# Argo_v2_Project.net
KiCad netlist of a schematic drawn in EasyEDA Pro
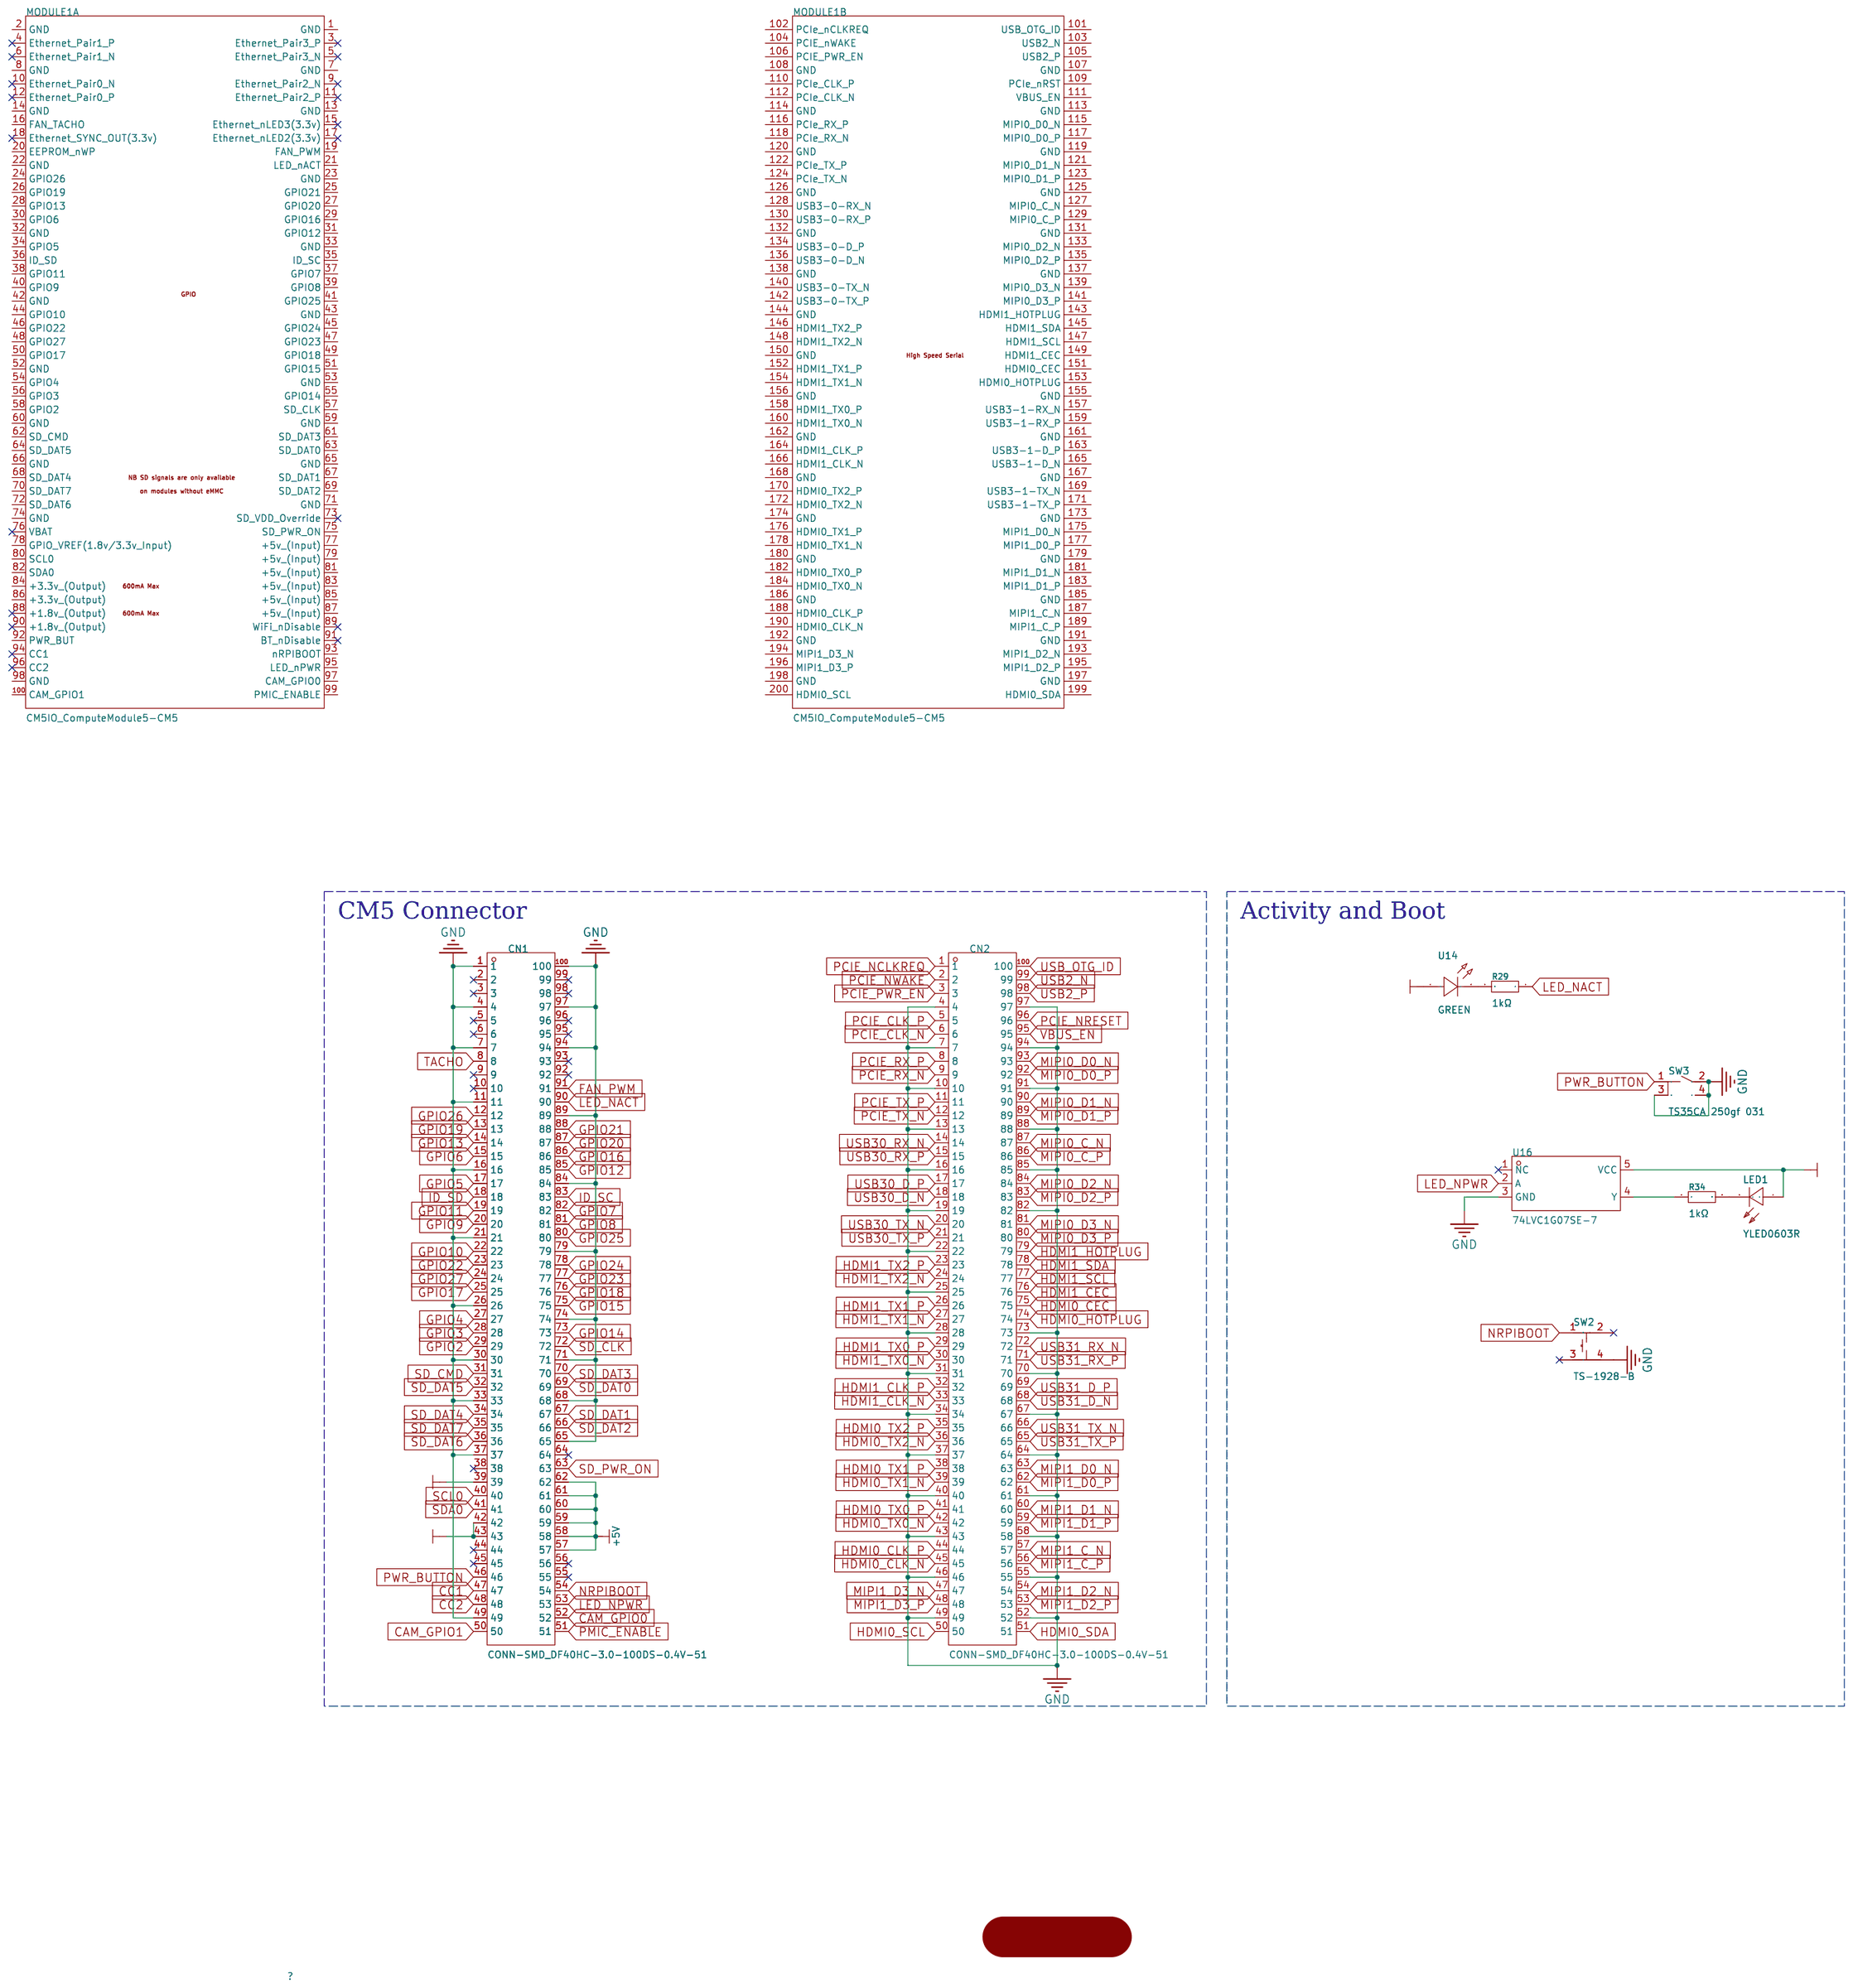
[diagram p0: schematic sheet]

(export (version "E")
  (design (tool "Eeschema 10.0.6"))
  (components
    (comp (ref "CN1")
      (value "CONN-SMD_DF40HC-3.0-100DS-0.4V-51")
      (footprint "easyedapro:CONN-SMD_DF40HC-3.0-100DS-0.4V-51")
      (fields (field (name "Manufacturer") "HRS(广濑)"))
      (libsource (lib "easyedapro") (part "DF40HC(3.0)-100DS-0.4V(51)"))
    )
    (comp (ref "CN2")
      (value "CONN-SMD_DF40HC-3.0-100DS-0.4V-51")
      (footprint "easyedapro:CONN-SMD_DF40HC-3.0-100DS-0.4V-51")
      (fields (field (name "Manufacturer") "HRS(广濑)"))
      (libsource (lib "easyedapro") (part "DF40HC(3.0)-100DS-0.4V(51)"))
    )
    (comp (ref "LED1")
      (value "YLED0603R")
      (footprint "easyedapro:LED0603-FD")
      (fields (field (name "Manufacturer") "YONGYUTAI(永裕泰)"))
      (libsource (lib "easyedapro") (part "YLED0603R"))
    )
    (comp (ref "MODULE1")
      (value "ComputeModule5-CM5")
      (footprint "easyedapro:CM5IO:Raspberry-Pi-5-Compute-Module")
      (libsource (lib "easyedapro") (part "CM5IO_ComputeModule5-CM5"))
    )
    (comp (ref "R29")
      (value "1kΩ")
      (footprint "easyedapro:R0402")
      (fields
        (field (name "Manufacturer Part") "0402WGF1001TCE")
        (field (name "Manufacturer") "UNI-ROYAL(厚声)")
      )
      (libsource (lib "easyedapro") (part "0402WGF1001TCE"))
    )
    (comp (ref "R34")
      (value "1kΩ")
      (footprint "easyedapro:R0402")
      (fields
        (field (name "Manufacturer Part") "0402WGF1001TCE")
        (field (name "Manufacturer") "UNI-ROYAL(厚声)")
      )
      (libsource (lib "easyedapro") (part "0402WGF1001TCE"))
    )
    (comp (ref "SW2")
      (value "TS-1928-B")
      (footprint "easyedapro:KEY-SMD_4P-L2.8-W2.0-P1.20-LS3.0-TL")
      (fields (field (name "Manufacturer") "XKB Connectivity(中国星坤)"))
      (libsource (lib "easyedapro") (part "TS-1928-B"))
    )
    (comp (ref "SW3")
      (value "TS35CA 250gf 031")
      (footprint "easyedapro:KEY-SMD_TS35CA-100GF-031")
      (fields (field (name "Manufacturer") "SHOU HAN(首韩)"))
      (libsource (lib "easyedapro") (part "TS35CA 250GF 031"))
    )
    (comp (ref "U14")
      (value "GREEN")
      (footprint "easyedapro:LED0603-FD")
      (fields (field (name "Manufacturer") "YONGYUTAI(永裕泰)"))
      (libsource (lib "easyedapro") (part "YLED0603G"))
    )
    (comp (ref "U16")
      (value "74LVC1G07SE-7")
      (footprint "easyedapro:SC-88A_L2.0-W1.3-P0.65-LS2.1-BL")
      (fields (field (name "Manufacturer") "DIODES(美台)"))
      (libsource (lib "easyedapro") (part "74LVC1G07SE-7"))
    )
  )
  (nets
    (net (code "1") (name "+3V3") (class "Default")
      (node (ref "CN1") (pin "39") (pinfunction "39_39") (pintype "unspecified"))
      (node (ref "CN1") (pin "42") (pinfunction "42_42") (pintype "unspecified"))
      (node (ref "CN1") (pin "43") (pinfunction "43_43") (pintype "unspecified"))
      (node (ref "LED1") (pin "1") (pinfunction "+_1") (pintype "unspecified"))
      (node (ref "U14") (pin "1") (pinfunction "+_1") (pintype "unspecified"))
      (node (ref "U16") (pin "5") (pinfunction "VCC_5") (pintype "unspecified"))
    )
    (net (code "2") (name "+5V") (class "Default")
      (node (ref "CN1") (pin "57") (pinfunction "57_57") (pintype "unspecified"))
      (node (ref "CN1") (pin "58") (pinfunction "58_58") (pintype "unspecified"))
      (node (ref "CN1") (pin "59") (pinfunction "59_59") (pintype "unspecified"))
      (node (ref "CN1") (pin "60") (pinfunction "60_60") (pintype "unspecified"))
      (node (ref "CN1") (pin "61") (pinfunction "61_61") (pintype "unspecified"))
      (node (ref "CN1") (pin "62") (pinfunction "62_62") (pintype "unspecified"))
    )
    (net (code "3") (name "CAM_GPIO0") (class "Default")
      (node (ref "CN1") (pin "52") (pinfunction "52_52") (pintype "unspecified"))
    )
    (net (code "4") (name "CAM_GPIO1") (class "Default")
      (node (ref "CN1") (pin "50") (pinfunction "50_50") (pintype "unspecified"))
    )
    (net (code "5") (name "CC1") (class "Default")
      (node (ref "CN1") (pin "47") (pinfunction "47_47") (pintype "unspecified"))
    )
    (net (code "6") (name "CC2") (class "Default")
      (node (ref "CN1") (pin "48") (pinfunction "48_48") (pintype "unspecified"))
    )
    (net (code "7") (name "FAN_PWM") (class "Default")
      (node (ref "CN1") (pin "91") (pinfunction "91_91") (pintype "unspecified"))
    )
    (net (code "8") (name "GND") (class "Default")
      (node (ref "CN1") (pin "1") (pinfunction "1_1") (pintype "unspecified"))
      (node (ref "CN1") (pin "100") (pinfunction "100_100") (pintype "unspecified"))
      (node (ref "CN1") (pin "11") (pinfunction "11_11") (pintype "unspecified"))
      (node (ref "CN1") (pin "16") (pinfunction "16_16") (pintype "unspecified"))
      (node (ref "CN1") (pin "21") (pinfunction "21_21") (pintype "unspecified"))
      (node (ref "CN1") (pin "26") (pinfunction "26_26") (pintype "unspecified"))
      (node (ref "CN1") (pin "30") (pinfunction "30_30") (pintype "unspecified"))
      (node (ref "CN1") (pin "33") (pinfunction "33_33") (pintype "unspecified"))
      (node (ref "CN1") (pin "37") (pinfunction "37_37") (pintype "unspecified"))
      (node (ref "CN1") (pin "4") (pinfunction "4_4") (pintype "unspecified"))
      (node (ref "CN1") (pin "49") (pinfunction "49_49") (pintype "unspecified"))
      (node (ref "CN1") (pin "65") (pinfunction "65_65") (pintype "unspecified"))
      (node (ref "CN1") (pin "68") (pinfunction "68_68") (pintype "unspecified"))
      (node (ref "CN1") (pin "7") (pinfunction "7_7") (pintype "unspecified"))
      (node (ref "CN1") (pin "71") (pinfunction "71_71") (pintype "unspecified"))
      (node (ref "CN1") (pin "74") (pinfunction "74_74") (pintype "unspecified"))
      (node (ref "CN1") (pin "79") (pinfunction "79_79") (pintype "unspecified"))
      (node (ref "CN1") (pin "84") (pinfunction "84_84") (pintype "unspecified"))
      (node (ref "CN1") (pin "89") (pinfunction "89_89") (pintype "unspecified"))
      (node (ref "CN1") (pin "94") (pinfunction "94_94") (pintype "unspecified"))
      (node (ref "CN1") (pin "97") (pinfunction "97_97") (pintype "unspecified"))
      (node (ref "CN2") (pin "10") (pinfunction "10_10") (pintype "unspecified"))
      (node (ref "CN2") (pin "13") (pinfunction "13_13") (pintype "unspecified"))
      (node (ref "CN2") (pin "16") (pinfunction "16_16") (pintype "unspecified"))
      (node (ref "CN2") (pin "19") (pinfunction "19_19") (pintype "unspecified"))
      (node (ref "CN2") (pin "22") (pinfunction "22_22") (pintype "unspecified"))
      (node (ref "CN2") (pin "25") (pinfunction "25_25") (pintype "unspecified"))
      (node (ref "CN2") (pin "28") (pinfunction "28_28") (pintype "unspecified"))
      (node (ref "CN2") (pin "31") (pinfunction "31_31") (pintype "unspecified"))
      (node (ref "CN2") (pin "34") (pinfunction "34_34") (pintype "unspecified"))
      (node (ref "CN2") (pin "37") (pinfunction "37_37") (pintype "unspecified"))
      (node (ref "CN2") (pin "4") (pinfunction "4_4") (pintype "unspecified"))
      (node (ref "CN2") (pin "40") (pinfunction "40_40") (pintype "unspecified"))
      (node (ref "CN2") (pin "43") (pinfunction "43_43") (pintype "unspecified"))
      (node (ref "CN2") (pin "46") (pinfunction "46_46") (pintype "unspecified"))
      (node (ref "CN2") (pin "49") (pinfunction "49_49") (pintype "unspecified"))
      (node (ref "CN2") (pin "52") (pinfunction "52_52") (pintype "unspecified"))
      (node (ref "CN2") (pin "55") (pinfunction "55_55") (pintype "unspecified"))
      (node (ref "CN2") (pin "58") (pinfunction "58_58") (pintype "unspecified"))
      (node (ref "CN2") (pin "61") (pinfunction "61_61") (pintype "unspecified"))
      (node (ref "CN2") (pin "64") (pinfunction "64_64") (pintype "unspecified"))
      (node (ref "CN2") (pin "67") (pinfunction "67_67") (pintype "unspecified"))
      (node (ref "CN2") (pin "7") (pinfunction "7_7") (pintype "unspecified"))
      (node (ref "CN2") (pin "70") (pinfunction "70_70") (pintype "unspecified"))
      (node (ref "CN2") (pin "73") (pinfunction "73_73") (pintype "unspecified"))
      (node (ref "CN2") (pin "82") (pinfunction "82_82") (pintype "unspecified"))
      (node (ref "CN2") (pin "85") (pinfunction "85_85") (pintype "unspecified"))
      (node (ref "CN2") (pin "88") (pinfunction "88_88") (pintype "unspecified"))
      (node (ref "CN2") (pin "91") (pinfunction "91_91") (pintype "unspecified"))
      (node (ref "CN2") (pin "94") (pinfunction "94_94") (pintype "unspecified"))
      (node (ref "CN2") (pin "97") (pinfunction "97_97") (pintype "unspecified"))
      (node (ref "SW2") (pin "4") (pinfunction "4_4") (pintype "input"))
      (node (ref "SW3") (pin "2") (pinfunction "2_2") (pintype "unspecified"))
      (node (ref "SW3") (pin "3") (pinfunction "3_3") (pintype "unspecified"))
      (node (ref "SW3") (pin "4") (pinfunction "4_4") (pintype "unspecified"))
      (node (ref "U16") (pin "3") (pinfunction "GND_3") (pintype "unspecified"))
    )
    (net (code "9") (name "GPIO2") (class "Default")
      (node (ref "CN1") (pin "29") (pinfunction "29_29") (pintype "unspecified"))
    )
    (net (code "10") (name "GPIO3") (class "Default")
      (node (ref "CN1") (pin "28") (pinfunction "28_28") (pintype "unspecified"))
    )
    (net (code "11") (name "GPIO4") (class "Default")
      (node (ref "CN1") (pin "27") (pinfunction "27_27") (pintype "unspecified"))
    )
    (net (code "12") (name "GPIO5") (class "Default")
      (node (ref "CN1") (pin "17") (pinfunction "17_17") (pintype "unspecified"))
    )
    (net (code "13") (name "GPIO6") (class "Default")
      (node (ref "CN1") (pin "15") (pinfunction "15_15") (pintype "unspecified"))
    )
    (net (code "14") (name "GPIO7") (class "Default")
      (node (ref "CN1") (pin "82") (pinfunction "82_82") (pintype "unspecified"))
    )
    (net (code "15") (name "GPIO8") (class "Default")
      (node (ref "CN1") (pin "81") (pinfunction "81_81") (pintype "unspecified"))
    )
    (net (code "16") (name "GPIO9") (class "Default")
      (node (ref "CN1") (pin "20") (pinfunction "20_20") (pintype "unspecified"))
    )
    (net (code "17") (name "GPIO10") (class "Default")
      (node (ref "CN1") (pin "22") (pinfunction "22_22") (pintype "unspecified"))
    )
    (net (code "18") (name "GPIO11") (class "Default")
      (node (ref "CN1") (pin "19") (pinfunction "19_19") (pintype "unspecified"))
    )
    (net (code "19") (name "GPIO12") (class "Default")
      (node (ref "CN1") (pin "85") (pinfunction "85_85") (pintype "unspecified"))
    )
    (net (code "20") (name "GPIO13") (class "Default")
      (node (ref "CN1") (pin "14") (pinfunction "14_14") (pintype "unspecified"))
    )
    (net (code "21") (name "GPIO14") (class "Default")
      (node (ref "CN1") (pin "73") (pinfunction "73_73") (pintype "unspecified"))
    )
    (net (code "22") (name "GPIO15") (class "Default")
      (node (ref "CN1") (pin "75") (pinfunction "75_75") (pintype "unspecified"))
    )
    (net (code "23") (name "GPIO16") (class "Default")
      (node (ref "CN1") (pin "86") (pinfunction "86_86") (pintype "unspecified"))
    )
    (net (code "24") (name "GPIO17") (class "Default")
      (node (ref "CN1") (pin "25") (pinfunction "25_25") (pintype "unspecified"))
    )
    (net (code "25") (name "GPIO18") (class "Default")
      (node (ref "CN1") (pin "76") (pinfunction "76_76") (pintype "unspecified"))
    )
    (net (code "26") (name "GPIO19") (class "Default")
      (node (ref "CN1") (pin "13") (pinfunction "13_13") (pintype "unspecified"))
    )
    (net (code "27") (name "GPIO20") (class "Default")
      (node (ref "CN1") (pin "87") (pinfunction "87_87") (pintype "unspecified"))
    )
    (net (code "28") (name "GPIO21") (class "Default")
      (node (ref "CN1") (pin "88") (pinfunction "88_88") (pintype "unspecified"))
    )
    (net (code "29") (name "GPIO22") (class "Default")
      (node (ref "CN1") (pin "23") (pinfunction "23_23") (pintype "unspecified"))
    )
    (net (code "30") (name "GPIO23") (class "Default")
      (node (ref "CN1") (pin "77") (pinfunction "77_77") (pintype "unspecified"))
    )
    (net (code "31") (name "GPIO24") (class "Default")
      (node (ref "CN1") (pin "78") (pinfunction "78_78") (pintype "unspecified"))
    )
    (net (code "32") (name "GPIO25") (class "Default")
      (node (ref "CN1") (pin "80") (pinfunction "80_80") (pintype "unspecified"))
    )
    (net (code "33") (name "GPIO26") (class "Default")
      (node (ref "CN1") (pin "12") (pinfunction "12_12") (pintype "unspecified"))
    )
    (net (code "34") (name "GPIO27") (class "Default")
      (node (ref "CN1") (pin "24") (pinfunction "24_24") (pintype "unspecified"))
    )
    (net (code "35") (name "HDMI0_CEC") (class "Default")
      (node (ref "CN2") (pin "75") (pinfunction "75_75") (pintype "unspecified"))
    )
    (net (code "36") (name "HDMI0_CLK_N") (class "Default")
      (node (ref "CN2") (pin "45") (pinfunction "45_45") (pintype "unspecified"))
    )
    (net (code "37") (name "HDMI0_CLK_P") (class "Default")
      (node (ref "CN2") (pin "44") (pinfunction "44_44") (pintype "unspecified"))
    )
    (net (code "38") (name "HDMI0_HOTPLUG") (class "Default")
      (node (ref "CN2") (pin "74") (pinfunction "74_74") (pintype "unspecified"))
    )
    (net (code "39") (name "HDMI0_SCL") (class "Default")
      (node (ref "CN2") (pin "50") (pinfunction "50_50") (pintype "unspecified"))
    )
    (net (code "40") (name "HDMI0_SDA") (class "Default")
      (node (ref "CN2") (pin "51") (pinfunction "51_51") (pintype "unspecified"))
    )
    (net (code "41") (name "HDMI0_TX0_N") (class "Default")
      (node (ref "CN2") (pin "42") (pinfunction "42_42") (pintype "unspecified"))
    )
    (net (code "42") (name "HDMI0_TX0_P") (class "Default")
      (node (ref "CN2") (pin "41") (pinfunction "41_41") (pintype "unspecified"))
    )
    (net (code "43") (name "HDMI0_TX1_N") (class "Default")
      (node (ref "CN2") (pin "39") (pinfunction "39_39") (pintype "unspecified"))
    )
    (net (code "44") (name "HDMI0_TX1_P") (class "Default")
      (node (ref "CN2") (pin "38") (pinfunction "38_38") (pintype "unspecified"))
    )
    (net (code "45") (name "HDMI0_TX2_N") (class "Default")
      (node (ref "CN2") (pin "36") (pinfunction "36_36") (pintype "unspecified"))
    )
    (net (code "46") (name "HDMI0_TX2_P") (class "Default")
      (node (ref "CN2") (pin "35") (pinfunction "35_35") (pintype "unspecified"))
    )
    (net (code "47") (name "HDMI1_CEC") (class "Default")
      (node (ref "CN2") (pin "76") (pinfunction "76_76") (pintype "unspecified"))
    )
    (net (code "48") (name "HDMI1_CLK_N") (class "Default")
      (node (ref "CN2") (pin "33") (pinfunction "33_33") (pintype "unspecified"))
    )
    (net (code "49") (name "HDMI1_CLK_P") (class "Default")
      (node (ref "CN2") (pin "32") (pinfunction "32_32") (pintype "unspecified"))
    )
    (net (code "50") (name "HDMI1_HOTPLUG") (class "Default")
      (node (ref "CN2") (pin "79") (pinfunction "79_79") (pintype "unspecified"))
    )
    (net (code "51") (name "HDMI1_SCL") (class "Default")
      (node (ref "CN2") (pin "77") (pinfunction "77_77") (pintype "unspecified"))
    )
    (net (code "52") (name "HDMI1_SDA") (class "Default")
      (node (ref "CN2") (pin "78") (pinfunction "78_78") (pintype "unspecified"))
    )
    (net (code "53") (name "HDMI1_TX0_N") (class "Default")
      (node (ref "CN2") (pin "30") (pinfunction "30_30") (pintype "unspecified"))
    )
    (net (code "54") (name "HDMI1_TX0_P") (class "Default")
      (node (ref "CN2") (pin "29") (pinfunction "29_29") (pintype "unspecified"))
    )
    (net (code "55") (name "HDMI1_TX1_N") (class "Default")
      (node (ref "CN2") (pin "27") (pinfunction "27_27") (pintype "unspecified"))
    )
    (net (code "56") (name "HDMI1_TX1_P") (class "Default")
      (node (ref "CN2") (pin "26") (pinfunction "26_26") (pintype "unspecified"))
    )
    (net (code "57") (name "HDMI1_TX2_N") (class "Default")
      (node (ref "CN2") (pin "24") (pinfunction "24_24") (pintype "unspecified"))
    )
    (net (code "58") (name "HDMI1_TX2_P") (class "Default")
      (node (ref "CN2") (pin "23") (pinfunction "23_23") (pintype "unspecified"))
    )
    (net (code "59") (name "ID_SC") (class "Default")
      (node (ref "CN1") (pin "83") (pinfunction "83_83") (pintype "unspecified"))
    )
    (net (code "60") (name "ID_SD") (class "Default")
      (node (ref "CN1") (pin "18") (pinfunction "18_18") (pintype "unspecified"))
    )
    (net (code "61") (name "LED_NACT") (class "Default")
      (node (ref "CN1") (pin "90") (pinfunction "90_90") (pintype "unspecified"))
      (node (ref "R29") (pin "1") (pinfunction "1_1") (pintype "input"))
    )
    (net (code "62") (name "LED_NPWR") (class "Default")
      (node (ref "CN1") (pin "53") (pinfunction "53_53") (pintype "unspecified"))
      (node (ref "U16") (pin "2") (pinfunction "A_2") (pintype "unspecified"))
    )
    (net (code "63") (name "MIPI0_C_N") (class "Default")
      (node (ref "CN2") (pin "87") (pinfunction "87_87") (pintype "unspecified"))
    )
    (net (code "64") (name "MIPI0_C_P") (class "Default")
      (node (ref "CN2") (pin "86") (pinfunction "86_86") (pintype "unspecified"))
    )
    (net (code "65") (name "MIPI0_D0_N") (class "Default")
      (node (ref "CN2") (pin "93") (pinfunction "93_93") (pintype "unspecified"))
    )
    (net (code "66") (name "MIPI0_D0_P") (class "Default")
      (node (ref "CN2") (pin "92") (pinfunction "92_92") (pintype "unspecified"))
    )
    (net (code "67") (name "MIPI0_D1_N") (class "Default")
      (node (ref "CN2") (pin "90") (pinfunction "90_90") (pintype "unspecified"))
    )
    (net (code "68") (name "MIPI0_D1_P") (class "Default")
      (node (ref "CN2") (pin "89") (pinfunction "89_89") (pintype "unspecified"))
    )
    (net (code "69") (name "MIPI0_D2_N") (class "Default")
      (node (ref "CN2") (pin "84") (pinfunction "84_84") (pintype "unspecified"))
    )
    (net (code "70") (name "MIPI0_D2_P") (class "Default")
      (node (ref "CN2") (pin "83") (pinfunction "83_83") (pintype "unspecified"))
    )
    (net (code "71") (name "MIPI0_D3_N") (class "Default")
      (node (ref "CN2") (pin "81") (pinfunction "81_81") (pintype "unspecified"))
    )
    (net (code "72") (name "MIPI0_D3_P") (class "Default")
      (node (ref "CN2") (pin "80") (pinfunction "80_80") (pintype "unspecified"))
    )
    (net (code "73") (name "MIPI1_C_N") (class "Default")
      (node (ref "CN2") (pin "57") (pinfunction "57_57") (pintype "unspecified"))
    )
    (net (code "74") (name "MIPI1_C_P") (class "Default")
      (node (ref "CN2") (pin "56") (pinfunction "56_56") (pintype "unspecified"))
    )
    (net (code "75") (name "MIPI1_D0_N") (class "Default")
      (node (ref "CN2") (pin "63") (pinfunction "63_63") (pintype "unspecified"))
    )
    (net (code "76") (name "MIPI1_D0_P") (class "Default")
      (node (ref "CN2") (pin "62") (pinfunction "62_62") (pintype "unspecified"))
    )
    (net (code "77") (name "MIPI1_D1_N") (class "Default")
      (node (ref "CN2") (pin "60") (pinfunction "60_60") (pintype "unspecified"))
    )
    (net (code "78") (name "MIPI1_D1_P") (class "Default")
      (node (ref "CN2") (pin "59") (pinfunction "59_59") (pintype "unspecified"))
    )
    (net (code "79") (name "MIPI1_D2_N") (class "Default")
      (node (ref "CN2") (pin "54") (pinfunction "54_54") (pintype "unspecified"))
    )
    (net (code "80") (name "MIPI1_D2_P") (class "Default")
      (node (ref "CN2") (pin "53") (pinfunction "53_53") (pintype "unspecified"))
    )
    (net (code "81") (name "MIPI1_D3_N") (class "Default")
      (node (ref "CN2") (pin "47") (pinfunction "47_47") (pintype "unspecified"))
    )
    (net (code "82") (name "MIPI1_D3_P") (class "Default")
      (node (ref "CN2") (pin "48") (pinfunction "48_48") (pintype "unspecified"))
    )
    (net (code "83") (name "NRPIBOOT") (class "Default")
      (node (ref "CN1") (pin "54") (pinfunction "54_54") (pintype "unspecified"))
      (node (ref "SW2") (pin "1") (pinfunction "1_1") (pintype "input"))
    )
    (net (code "84") (name "Net-(LED1--)") (class "Default")
      (node (ref "LED1") (pin "2") (pinfunction "-_2") (pintype "unspecified"))
      (node (ref "R34") (pin "2") (pinfunction "2_2") (pintype "input"))
    )
    (net (code "85") (name "Net-(U14--)") (class "Default")
      (node (ref "R29") (pin "2") (pinfunction "2_2") (pintype "input"))
      (node (ref "U14") (pin "2") (pinfunction "-_2") (pintype "unspecified"))
    )
    (net (code "86") (name "Net-(U16-Y)") (class "Default")
      (node (ref "R34") (pin "1") (pinfunction "1_1") (pintype "input"))
      (node (ref "U16") (pin "4") (pinfunction "Y_4") (pintype "unspecified"))
    )
    (net (code "87") (name "PCIE_CLK_N") (class "Default")
      (node (ref "CN2") (pin "6") (pinfunction "6_6") (pintype "unspecified"))
    )
    (net (code "88") (name "PCIE_CLK_P") (class "Default")
      (node (ref "CN2") (pin "5") (pinfunction "5_5") (pintype "unspecified"))
    )
    (net (code "89") (name "PCIE_NCLKREQ") (class "Default")
      (node (ref "CN2") (pin "1") (pinfunction "1_1") (pintype "unspecified"))
    )
    (net (code "90") (name "PCIE_NRESET") (class "Default")
      (node (ref "CN2") (pin "96") (pinfunction "96_96") (pintype "unspecified"))
    )
    (net (code "91") (name "PCIE_NWAKE") (class "Default")
      (node (ref "CN2") (pin "2") (pinfunction "2_2") (pintype "unspecified"))
    )
    (net (code "92") (name "PCIE_PWR_EN") (class "Default")
      (node (ref "CN2") (pin "3") (pinfunction "3_3") (pintype "unspecified"))
    )
    (net (code "93") (name "PCIE_RX_N") (class "Default")
      (node (ref "CN2") (pin "9") (pinfunction "9_9") (pintype "unspecified"))
    )
    (net (code "94") (name "PCIE_RX_P") (class "Default")
      (node (ref "CN2") (pin "8") (pinfunction "8_8") (pintype "unspecified"))
    )
    (net (code "95") (name "PCIE_TX_N") (class "Default")
      (node (ref "CN2") (pin "12") (pinfunction "12_12") (pintype "unspecified"))
    )
    (net (code "96") (name "PCIE_TX_P") (class "Default")
      (node (ref "CN2") (pin "11") (pinfunction "11_11") (pintype "unspecified"))
    )
    (net (code "97") (name "PMIC_ENABLE") (class "Default")
      (node (ref "CN1") (pin "51") (pinfunction "51_51") (pintype "unspecified"))
    )
    (net (code "98") (name "PWR_BUTTON") (class "Default")
      (node (ref "CN1") (pin "46") (pinfunction "46_46") (pintype "unspecified"))
      (node (ref "SW3") (pin "1") (pinfunction "1_1") (pintype "unspecified"))
    )
    (net (code "99") (name "SCL0") (class "Default")
      (node (ref "CN1") (pin "40") (pinfunction "40_40") (pintype "unspecified"))
    )
    (net (code "100") (name "SDA0") (class "Default")
      (node (ref "CN1") (pin "41") (pinfunction "41_41") (pintype "unspecified"))
    )
    (net (code "101") (name "SD_CLK") (class "Default")
      (node (ref "CN1") (pin "72") (pinfunction "72_72") (pintype "unspecified"))
    )
    (net (code "102") (name "SD_CMD") (class "Default")
      (node (ref "CN1") (pin "31") (pinfunction "31_31") (pintype "unspecified"))
    )
    (net (code "103") (name "SD_DAT0") (class "Default")
      (node (ref "CN1") (pin "69") (pinfunction "69_69") (pintype "unspecified"))
    )
    (net (code "104") (name "SD_DAT1") (class "Default")
      (node (ref "CN1") (pin "67") (pinfunction "67_67") (pintype "unspecified"))
    )
    (net (code "105") (name "SD_DAT2") (class "Default")
      (node (ref "CN1") (pin "66") (pinfunction "66_66") (pintype "unspecified"))
    )
    (net (code "106") (name "SD_DAT3") (class "Default")
      (node (ref "CN1") (pin "70") (pinfunction "70_70") (pintype "unspecified"))
    )
    (net (code "107") (name "SD_DAT4") (class "Default")
      (node (ref "CN1") (pin "34") (pinfunction "34_34") (pintype "unspecified"))
    )
    (net (code "108") (name "SD_DAT5") (class "Default")
      (node (ref "CN1") (pin "32") (pinfunction "32_32") (pintype "unspecified"))
    )
    (net (code "109") (name "SD_DAT6") (class "Default")
      (node (ref "CN1") (pin "36") (pinfunction "36_36") (pintype "unspecified"))
    )
    (net (code "110") (name "SD_DAT7") (class "Default")
      (node (ref "CN1") (pin "35") (pinfunction "35_35") (pintype "unspecified"))
    )
    (net (code "111") (name "SD_PWR_ON") (class "Default")
      (node (ref "CN1") (pin "63") (pinfunction "63_63") (pintype "unspecified"))
    )
    (net (code "112") (name "TACHO") (class "Default")
      (node (ref "CN1") (pin "8") (pinfunction "8_8") (pintype "unspecified"))
    )
    (net (code "113") (name "USB2_N") (class "Default")
      (node (ref "CN2") (pin "99") (pinfunction "99_99") (pintype "unspecified"))
    )
    (net (code "114") (name "USB2_P") (class "Default")
      (node (ref "CN2") (pin "98") (pinfunction "98_98") (pintype "unspecified"))
    )
    (net (code "115") (name "USB30_D_N") (class "Default")
      (node (ref "CN2") (pin "18") (pinfunction "18_18") (pintype "unspecified"))
    )
    (net (code "116") (name "USB30_D_P") (class "Default")
      (node (ref "CN2") (pin "17") (pinfunction "17_17") (pintype "unspecified"))
    )
    (net (code "117") (name "USB30_RX_N") (class "Default")
      (node (ref "CN2") (pin "14") (pinfunction "14_14") (pintype "unspecified"))
    )
    (net (code "118") (name "USB30_RX_P") (class "Default")
      (node (ref "CN2") (pin "15") (pinfunction "15_15") (pintype "unspecified"))
    )
    (net (code "119") (name "USB30_TX_N") (class "Default")
      (node (ref "CN2") (pin "20") (pinfunction "20_20") (pintype "unspecified"))
    )
    (net (code "120") (name "USB30_TX_P") (class "Default")
      (node (ref "CN2") (pin "21") (pinfunction "21_21") (pintype "unspecified"))
    )
    (net (code "121") (name "USB31_D_N") (class "Default")
      (node (ref "CN2") (pin "68") (pinfunction "68_68") (pintype "unspecified"))
    )
    (net (code "122") (name "USB31_D_P") (class "Default")
      (node (ref "CN2") (pin "69") (pinfunction "69_69") (pintype "unspecified"))
    )
    (net (code "123") (name "USB31_RX_N") (class "Default")
      (node (ref "CN2") (pin "72") (pinfunction "72_72") (pintype "unspecified"))
    )
    (net (code "124") (name "USB31_RX_P") (class "Default")
      (node (ref "CN2") (pin "71") (pinfunction "71_71") (pintype "unspecified"))
    )
    (net (code "125") (name "USB31_TX_N") (class "Default")
      (node (ref "CN2") (pin "66") (pinfunction "66_66") (pintype "unspecified"))
    )
    (net (code "126") (name "USB31_TX_P") (class "Default")
      (node (ref "CN2") (pin "65") (pinfunction "65_65") (pintype "unspecified"))
    )
    (net (code "127") (name "USB_OTG_ID") (class "Default")
      (node (ref "CN2") (pin "100") (pinfunction "100_100") (pintype "unspecified"))
    )
    (net (code "128") (name "VBUS_EN") (class "Default")
      (node (ref "CN2") (pin "95") (pinfunction "95_95") (pintype "unspecified"))
    )
    (net (code "129") (name "unconnected-(CN1-Pad2)") (class "Default")
      (node (ref "CN1") (pin "2") (pinfunction "2_2") (pintype "unspecified+no_connect"))
    )
    (net (code "130") (name "unconnected-(CN1-Pad3)") (class "Default")
      (node (ref "CN1") (pin "3") (pinfunction "3_3") (pintype "unspecified+no_connect"))
    )
    (net (code "131") (name "unconnected-(CN1-Pad5)") (class "Default")
      (node (ref "CN1") (pin "5") (pinfunction "5_5") (pintype "unspecified+no_connect"))
    )
    (net (code "132") (name "unconnected-(CN1-Pad6)") (class "Default")
      (node (ref "CN1") (pin "6") (pinfunction "6_6") (pintype "unspecified+no_connect"))
    )
    (net (code "133") (name "unconnected-(CN1-Pad9)") (class "Default")
      (node (ref "CN1") (pin "9") (pinfunction "9_9") (pintype "unspecified+no_connect"))
    )
    (net (code "134") (name "unconnected-(CN1-Pad10)") (class "Default")
      (node (ref "CN1") (pin "10") (pinfunction "10_10") (pintype "unspecified+no_connect"))
    )
    (net (code "135") (name "unconnected-(CN1-Pad38)") (class "Default")
      (node (ref "CN1") (pin "38") (pinfunction "38_38") (pintype "unspecified+no_connect"))
    )
    (net (code "136") (name "unconnected-(CN1-Pad44)") (class "Default")
      (node (ref "CN1") (pin "44") (pinfunction "44_44") (pintype "unspecified+no_connect"))
    )
    (net (code "137") (name "unconnected-(CN1-Pad45)") (class "Default")
      (node (ref "CN1") (pin "45") (pinfunction "45_45") (pintype "unspecified+no_connect"))
    )
    (net (code "138") (name "unconnected-(CN1-Pad55)") (class "Default")
      (node (ref "CN1") (pin "55") (pinfunction "55_55") (pintype "unspecified+no_connect"))
    )
    (net (code "139") (name "unconnected-(CN1-Pad56)") (class "Default")
      (node (ref "CN1") (pin "56") (pinfunction "56_56") (pintype "unspecified+no_connect"))
    )
    (net (code "140") (name "unconnected-(CN1-Pad64)") (class "Default")
      (node (ref "CN1") (pin "64") (pinfunction "64_64") (pintype "unspecified+no_connect"))
    )
    (net (code "141") (name "unconnected-(CN1-Pad92)") (class "Default")
      (node (ref "CN1") (pin "92") (pinfunction "92_92") (pintype "unspecified+no_connect"))
    )
    (net (code "142") (name "unconnected-(CN1-Pad93)") (class "Default")
      (node (ref "CN1") (pin "93") (pinfunction "93_93") (pintype "unspecified+no_connect"))
    )
    (net (code "143") (name "unconnected-(CN1-Pad95)") (class "Default")
      (node (ref "CN1") (pin "95") (pinfunction "95_95") (pintype "unspecified+no_connect"))
    )
    (net (code "144") (name "unconnected-(CN1-Pad96)") (class "Default")
      (node (ref "CN1") (pin "96") (pinfunction "96_96") (pintype "unspecified+no_connect"))
    )
    (net (code "145") (name "unconnected-(CN1-Pad98)") (class "Default")
      (node (ref "CN1") (pin "98") (pinfunction "98_98") (pintype "unspecified+no_connect"))
    )
    (net (code "146") (name "unconnected-(CN1-Pad99)") (class "Default")
      (node (ref "CN1") (pin "99") (pinfunction "99_99") (pintype "unspecified+no_connect"))
    )
    (net (code "147") (name "unconnected-(MODULE1A-+1.8v_(Output)-Pad88)") (class "Default")
      (node (ref "MODULE1") (pin "88") (pinfunction "+1.8v_(Output)_88") (pintype "unspecified+no_connect"))
    )
    (net (code "148") (name "unconnected-(MODULE1A-+1.8v_(Output)-Pad90)") (class "Default")
      (node (ref "MODULE1") (pin "90") (pinfunction "+1.8v_(Output)_90") (pintype "unspecified+no_connect"))
    )
    (net (code "149") (name "unconnected-(MODULE1A-+3.3v_(Output)-Pad84)") (class "Default")
      (node (ref "MODULE1") (pin "84") (pinfunction "+3.3v_(Output)_84") (pintype "unspecified"))
    )
    (net (code "150") (name "unconnected-(MODULE1A-+3.3v_(Output)-Pad86)") (class "Default")
      (node (ref "MODULE1") (pin "86") (pinfunction "+3.3v_(Output)_86") (pintype "unspecified"))
    )
    (net (code "151") (name "unconnected-(MODULE1A-+5v_(Input)-Pad77)") (class "Default")
      (node (ref "MODULE1") (pin "77") (pinfunction "+5v_(Input)_77") (pintype "unspecified"))
    )
    (net (code "152") (name "unconnected-(MODULE1A-+5v_(Input)-Pad79)") (class "Default")
      (node (ref "MODULE1") (pin "79") (pinfunction "+5v_(Input)_79") (pintype "unspecified"))
    )
    (net (code "153") (name "unconnected-(MODULE1A-+5v_(Input)-Pad81)") (class "Default")
      (node (ref "MODULE1") (pin "81") (pinfunction "+5v_(Input)_81") (pintype "unspecified"))
    )
    (net (code "154") (name "unconnected-(MODULE1A-+5v_(Input)-Pad83)") (class "Default")
      (node (ref "MODULE1") (pin "83") (pinfunction "+5v_(Input)_83") (pintype "unspecified"))
    )
    (net (code "155") (name "unconnected-(MODULE1A-+5v_(Input)-Pad85)") (class "Default")
      (node (ref "MODULE1") (pin "85") (pinfunction "+5v_(Input)_85") (pintype "unspecified"))
    )
    (net (code "156") (name "unconnected-(MODULE1A-+5v_(Input)-Pad87)") (class "Default")
      (node (ref "MODULE1") (pin "87") (pinfunction "+5v_(Input)_87") (pintype "unspecified"))
    )
    (net (code "157") (name "unconnected-(MODULE1A-BT_nDisable-Pad91)") (class "Default")
      (node (ref "MODULE1") (pin "91") (pinfunction "BT_nDisable_91") (pintype "input+no_connect"))
    )
    (net (code "158") (name "unconnected-(MODULE1A-CAM_GPIO0-Pad97)") (class "Default")
      (node (ref "MODULE1") (pin "97") (pinfunction "CAM_GPIO0_97") (pintype "unspecified"))
    )
    (net (code "159") (name "unconnected-(MODULE1A-CAM_GPIO1-Pad100)") (class "Default")
      (node (ref "MODULE1") (pin "100") (pinfunction "CAM_GPIO1_100") (pintype "unspecified"))
    )
    (net (code "160") (name "unconnected-(MODULE1A-CC1-Pad94)") (class "Default")
      (node (ref "MODULE1") (pin "94") (pinfunction "CC1_94") (pintype "unspecified+no_connect"))
    )
    (net (code "161") (name "unconnected-(MODULE1A-CC2-Pad96)") (class "Default")
      (node (ref "MODULE1") (pin "96") (pinfunction "CC2_96") (pintype "unspecified+no_connect"))
    )
    (net (code "162") (name "unconnected-(MODULE1A-EEPROM_nWP-Pad20)") (class "Default")
      (node (ref "MODULE1") (pin "20") (pinfunction "EEPROM_nWP_20") (pintype "unspecified"))
    )
    (net (code "163") (name "unconnected-(MODULE1A-Ethernet_Pair0_N-Pad10)") (class "Default")
      (node (ref "MODULE1") (pin "10") (pinfunction "Ethernet_Pair0_N_10") (pintype "unspecified+no_connect"))
    )
    (net (code "164") (name "unconnected-(MODULE1A-Ethernet_Pair0_P-Pad12)") (class "Default")
      (node (ref "MODULE1") (pin "12") (pinfunction "Ethernet_Pair0_P_12") (pintype "unspecified+no_connect"))
    )
    (net (code "165") (name "unconnected-(MODULE1A-Ethernet_Pair1_N-Pad6)") (class "Default")
      (node (ref "MODULE1") (pin "6") (pinfunction "Ethernet_Pair1_N_6") (pintype "unspecified+no_connect"))
    )
    (net (code "166") (name "unconnected-(MODULE1A-Ethernet_Pair1_P-Pad4)") (class "Default")
      (node (ref "MODULE1") (pin "4") (pinfunction "Ethernet_Pair1_P_4") (pintype "unspecified+no_connect"))
    )
    (net (code "167") (name "unconnected-(MODULE1A-Ethernet_Pair2_N-Pad9)") (class "Default")
      (node (ref "MODULE1") (pin "9") (pinfunction "Ethernet_Pair2_N_9") (pintype "unspecified+no_connect"))
    )
    (net (code "168") (name "unconnected-(MODULE1A-Ethernet_Pair2_P-Pad11)") (class "Default")
      (node (ref "MODULE1") (pin "11") (pinfunction "Ethernet_Pair2_P_11") (pintype "unspecified+no_connect"))
    )
    (net (code "169") (name "unconnected-(MODULE1A-Ethernet_Pair3_N-Pad5)") (class "Default")
      (node (ref "MODULE1") (pin "5") (pinfunction "Ethernet_Pair3_N_5") (pintype "unspecified+no_connect"))
    )
    (net (code "170") (name "unconnected-(MODULE1A-Ethernet_Pair3_P-Pad3)") (class "Default")
      (node (ref "MODULE1") (pin "3") (pinfunction "Ethernet_Pair3_P_3") (pintype "unspecified+no_connect"))
    )
    (net (code "171") (name "unconnected-(MODULE1A-Ethernet_SYNC_OUT(3.3v)-Pad18)") (class "Default")
      (node (ref "MODULE1") (pin "18") (pinfunction "Ethernet_SYNC_OUT(3.3v)_18") (pintype "input+no_connect"))
    )
    (net (code "172") (name "unconnected-(MODULE1A-Ethernet_nLED2(3.3v)-Pad17)") (class "Default")
      (node (ref "MODULE1") (pin "17") (pinfunction "Ethernet_nLED2(3.3v)_17") (pintype "output+no_connect"))
    )
    (net (code "173") (name "unconnected-(MODULE1A-Ethernet_nLED3(3.3v)-Pad15)") (class "Default")
      (node (ref "MODULE1") (pin "15") (pinfunction "Ethernet_nLED3(3.3v)_15") (pintype "output+no_connect"))
    )
    (net (code "174") (name "unconnected-(MODULE1A-FAN_PWM-Pad19)") (class "Default")
      (node (ref "MODULE1") (pin "19") (pinfunction "FAN_PWM_19") (pintype "output"))
    )
    (net (code "175") (name "unconnected-(MODULE1A-FAN_TACHO-Pad16)") (class "Default")
      (node (ref "MODULE1") (pin "16") (pinfunction "FAN_TACHO_16") (pintype "input"))
    )
    (net (code "176") (name "unconnected-(MODULE1A-GND-Pad1)") (class "Default")
      (node (ref "MODULE1") (pin "1") (pinfunction "GND_1") (pintype "unspecified"))
    )
    (net (code "177") (name "unconnected-(MODULE1A-GND-Pad2)") (class "Default")
      (node (ref "MODULE1") (pin "2") (pinfunction "GND_2") (pintype "unspecified"))
    )
    (net (code "178") (name "unconnected-(MODULE1A-GND-Pad7)") (class "Default")
      (node (ref "MODULE1") (pin "7") (pinfunction "GND_7") (pintype "unspecified"))
    )
    (net (code "179") (name "unconnected-(MODULE1A-GND-Pad8)") (class "Default")
      (node (ref "MODULE1") (pin "8") (pinfunction "GND_8") (pintype "unspecified"))
    )
    (net (code "180") (name "unconnected-(MODULE1A-GND-Pad13)") (class "Default")
      (node (ref "MODULE1") (pin "13") (pinfunction "GND_13") (pintype "unspecified"))
    )
    (net (code "181") (name "unconnected-(MODULE1A-GND-Pad14)") (class "Default")
      (node (ref "MODULE1") (pin "14") (pinfunction "GND_14") (pintype "unspecified"))
    )
    (net (code "182") (name "unconnected-(MODULE1A-GND-Pad22)") (class "Default")
      (node (ref "MODULE1") (pin "22") (pinfunction "GND_22") (pintype "unspecified"))
    )
    (net (code "183") (name "unconnected-(MODULE1A-GND-Pad23)") (class "Default")
      (node (ref "MODULE1") (pin "23") (pinfunction "GND_23") (pintype "unspecified"))
    )
    (net (code "184") (name "unconnected-(MODULE1A-GND-Pad32)") (class "Default")
      (node (ref "MODULE1") (pin "32") (pinfunction "GND_32") (pintype "unspecified"))
    )
    (net (code "185") (name "unconnected-(MODULE1A-GND-Pad33)") (class "Default")
      (node (ref "MODULE1") (pin "33") (pinfunction "GND_33") (pintype "unspecified"))
    )
    (net (code "186") (name "unconnected-(MODULE1A-GND-Pad42)") (class "Default")
      (node (ref "MODULE1") (pin "42") (pinfunction "GND_42") (pintype "unspecified"))
    )
    (net (code "187") (name "unconnected-(MODULE1A-GND-Pad43)") (class "Default")
      (node (ref "MODULE1") (pin "43") (pinfunction "GND_43") (pintype "unspecified"))
    )
    (net (code "188") (name "unconnected-(MODULE1A-GND-Pad52)") (class "Default")
      (node (ref "MODULE1") (pin "52") (pinfunction "GND_52") (pintype "unspecified"))
    )
    (net (code "189") (name "unconnected-(MODULE1A-GND-Pad53)") (class "Default")
      (node (ref "MODULE1") (pin "53") (pinfunction "GND_53") (pintype "unspecified"))
    )
    (net (code "190") (name "unconnected-(MODULE1A-GND-Pad59)") (class "Default")
      (node (ref "MODULE1") (pin "59") (pinfunction "GND_59") (pintype "unspecified"))
    )
    (net (code "191") (name "unconnected-(MODULE1A-GND-Pad60)") (class "Default")
      (node (ref "MODULE1") (pin "60") (pinfunction "GND_60") (pintype "unspecified"))
    )
    (net (code "192") (name "unconnected-(MODULE1A-GND-Pad65)") (class "Default")
      (node (ref "MODULE1") (pin "65") (pinfunction "GND_65") (pintype "unspecified"))
    )
    (net (code "193") (name "unconnected-(MODULE1A-GND-Pad66)") (class "Default")
      (node (ref "MODULE1") (pin "66") (pinfunction "GND_66") (pintype "unspecified"))
    )
    (net (code "194") (name "unconnected-(MODULE1A-GND-Pad71)") (class "Default")
      (node (ref "MODULE1") (pin "71") (pinfunction "GND_71") (pintype "unspecified"))
    )
    (net (code "195") (name "unconnected-(MODULE1A-GND-Pad74)") (class "Default")
      (node (ref "MODULE1") (pin "74") (pinfunction "GND_74") (pintype "unspecified"))
    )
    (net (code "196") (name "unconnected-(MODULE1A-GND-Pad98)") (class "Default")
      (node (ref "MODULE1") (pin "98") (pinfunction "GND_98") (pintype "unspecified"))
    )
    (net (code "197") (name "unconnected-(MODULE1A-GPIO2-Pad58)") (class "Default")
      (node (ref "MODULE1") (pin "58") (pinfunction "GPIO2_58") (pintype "unspecified"))
    )
    (net (code "198") (name "unconnected-(MODULE1A-GPIO3-Pad56)") (class "Default")
      (node (ref "MODULE1") (pin "56") (pinfunction "GPIO3_56") (pintype "unspecified"))
    )
    (net (code "199") (name "unconnected-(MODULE1A-GPIO4-Pad54)") (class "Default")
      (node (ref "MODULE1") (pin "54") (pinfunction "GPIO4_54") (pintype "unspecified"))
    )
    (net (code "200") (name "unconnected-(MODULE1A-GPIO5-Pad34)") (class "Default")
      (node (ref "MODULE1") (pin "34") (pinfunction "GPIO5_34") (pintype "unspecified"))
    )
    (net (code "201") (name "unconnected-(MODULE1A-GPIO6-Pad30)") (class "Default")
      (node (ref "MODULE1") (pin "30") (pinfunction "GPIO6_30") (pintype "unspecified"))
    )
    (net (code "202") (name "unconnected-(MODULE1A-GPIO7-Pad37)") (class "Default")
      (node (ref "MODULE1") (pin "37") (pinfunction "GPIO7_37") (pintype "unspecified"))
    )
    (net (code "203") (name "unconnected-(MODULE1A-GPIO8-Pad39)") (class "Default")
      (node (ref "MODULE1") (pin "39") (pinfunction "GPIO8_39") (pintype "unspecified"))
    )
    (net (code "204") (name "unconnected-(MODULE1A-GPIO9-Pad40)") (class "Default")
      (node (ref "MODULE1") (pin "40") (pinfunction "GPIO9_40") (pintype "unspecified"))
    )
    (net (code "205") (name "unconnected-(MODULE1A-GPIO10-Pad44)") (class "Default")
      (node (ref "MODULE1") (pin "44") (pinfunction "GPIO10_44") (pintype "unspecified"))
    )
    (net (code "206") (name "unconnected-(MODULE1A-GPIO11-Pad38)") (class "Default")
      (node (ref "MODULE1") (pin "38") (pinfunction "GPIO11_38") (pintype "unspecified"))
    )
    (net (code "207") (name "unconnected-(MODULE1A-GPIO12-Pad31)") (class "Default")
      (node (ref "MODULE1") (pin "31") (pinfunction "GPIO12_31") (pintype "unspecified"))
    )
    (net (code "208") (name "unconnected-(MODULE1A-GPIO13-Pad28)") (class "Default")
      (node (ref "MODULE1") (pin "28") (pinfunction "GPIO13_28") (pintype "unspecified"))
    )
    (net (code "209") (name "unconnected-(MODULE1A-GPIO14-Pad55)") (class "Default")
      (node (ref "MODULE1") (pin "55") (pinfunction "GPIO14_55") (pintype "unspecified"))
    )
    (net (code "210") (name "unconnected-(MODULE1A-GPIO15-Pad51)") (class "Default")
      (node (ref "MODULE1") (pin "51") (pinfunction "GPIO15_51") (pintype "unspecified"))
    )
    (net (code "211") (name "unconnected-(MODULE1A-GPIO16-Pad29)") (class "Default")
      (node (ref "MODULE1") (pin "29") (pinfunction "GPIO16_29") (pintype "unspecified"))
    )
    (net (code "212") (name "unconnected-(MODULE1A-GPIO17-Pad50)") (class "Default")
      (node (ref "MODULE1") (pin "50") (pinfunction "GPIO17_50") (pintype "unspecified"))
    )
    (net (code "213") (name "unconnected-(MODULE1A-GPIO18-Pad49)") (class "Default")
      (node (ref "MODULE1") (pin "49") (pinfunction "GPIO18_49") (pintype "unspecified"))
    )
    (net (code "214") (name "unconnected-(MODULE1A-GPIO19-Pad26)") (class "Default")
      (node (ref "MODULE1") (pin "26") (pinfunction "GPIO19_26") (pintype "unspecified"))
    )
    (net (code "215") (name "unconnected-(MODULE1A-GPIO20-Pad27)") (class "Default")
      (node (ref "MODULE1") (pin "27") (pinfunction "GPIO20_27") (pintype "unspecified"))
    )
    (net (code "216") (name "unconnected-(MODULE1A-GPIO21-Pad25)") (class "Default")
      (node (ref "MODULE1") (pin "25") (pinfunction "GPIO21_25") (pintype "unspecified"))
    )
    (net (code "217") (name "unconnected-(MODULE1A-GPIO22-Pad46)") (class "Default")
      (node (ref "MODULE1") (pin "46") (pinfunction "GPIO22_46") (pintype "unspecified"))
    )
    (net (code "218") (name "unconnected-(MODULE1A-GPIO23-Pad47)") (class "Default")
      (node (ref "MODULE1") (pin "47") (pinfunction "GPIO23_47") (pintype "unspecified"))
    )
    (net (code "219") (name "unconnected-(MODULE1A-GPIO24-Pad45)") (class "Default")
      (node (ref "MODULE1") (pin "45") (pinfunction "GPIO24_45") (pintype "unspecified"))
    )
    (net (code "220") (name "unconnected-(MODULE1A-GPIO25-Pad41)") (class "Default")
      (node (ref "MODULE1") (pin "41") (pinfunction "GPIO25_41") (pintype "unspecified"))
    )
    (net (code "221") (name "unconnected-(MODULE1A-GPIO26-Pad24)") (class "Default")
      (node (ref "MODULE1") (pin "24") (pinfunction "GPIO26_24") (pintype "unspecified"))
    )
    (net (code "222") (name "unconnected-(MODULE1A-GPIO27-Pad48)") (class "Default")
      (node (ref "MODULE1") (pin "48") (pinfunction "GPIO27_48") (pintype "unspecified"))
    )
    (net (code "223") (name "unconnected-(MODULE1A-GPIO_VREF(1.8v{slash}3.3v_Input)-Pad78)") (class "Default")
      (node (ref "MODULE1") (pin "78") (pinfunction "GPIO_VREF(1.8v/3.3v_Input)_78") (pintype "unspecified"))
    )
    (net (code "224") (name "unconnected-(MODULE1A-ID_SC-Pad35)") (class "Default")
      (node (ref "MODULE1") (pin "35") (pinfunction "ID_SC_35") (pintype "unspecified"))
    )
    (net (code "225") (name "unconnected-(MODULE1A-ID_SD-Pad36)") (class "Default")
      (node (ref "MODULE1") (pin "36") (pinfunction "ID_SD_36") (pintype "unspecified"))
    )
    (net (code "226") (name "unconnected-(MODULE1A-LED_nACT-Pad21)") (class "Default")
      (node (ref "MODULE1") (pin "21") (pinfunction "LED_nACT_21") (pintype "unspecified"))
    )
    (net (code "227") (name "unconnected-(MODULE1A-LED_nPWR-Pad95)") (class "Default")
      (node (ref "MODULE1") (pin "95") (pinfunction "LED_nPWR_95") (pintype "output"))
    )
    (net (code "228") (name "unconnected-(MODULE1A-PMIC_ENABLE-Pad99)") (class "Default")
      (node (ref "MODULE1") (pin "99") (pinfunction "PMIC_ENABLE_99") (pintype "input"))
    )
    (net (code "229") (name "unconnected-(MODULE1A-PWR_BUT-Pad92)") (class "Default")
      (node (ref "MODULE1") (pin "92") (pinfunction "PWR_BUT_92") (pintype "unspecified"))
    )
    (net (code "230") (name "unconnected-(MODULE1A-SCL0-Pad80)") (class "Default")
      (node (ref "MODULE1") (pin "80") (pinfunction "SCL0_80") (pintype "unspecified"))
    )
    (net (code "231") (name "unconnected-(MODULE1A-SDA0-Pad82)") (class "Default")
      (node (ref "MODULE1") (pin "82") (pinfunction "SDA0_82") (pintype "unspecified"))
    )
    (net (code "232") (name "unconnected-(MODULE1A-SD_CLK-Pad57)") (class "Default")
      (node (ref "MODULE1") (pin "57") (pinfunction "SD_CLK_57") (pintype "unspecified"))
    )
    (net (code "233") (name "unconnected-(MODULE1A-SD_CMD-Pad62)") (class "Default")
      (node (ref "MODULE1") (pin "62") (pinfunction "SD_CMD_62") (pintype "unspecified"))
    )
    (net (code "234") (name "unconnected-(MODULE1A-SD_DAT0-Pad63)") (class "Default")
      (node (ref "MODULE1") (pin "63") (pinfunction "SD_DAT0_63") (pintype "unspecified"))
    )
    (net (code "235") (name "unconnected-(MODULE1A-SD_DAT1-Pad67)") (class "Default")
      (node (ref "MODULE1") (pin "67") (pinfunction "SD_DAT1_67") (pintype "unspecified"))
    )
    (net (code "236") (name "unconnected-(MODULE1A-SD_DAT2-Pad69)") (class "Default")
      (node (ref "MODULE1") (pin "69") (pinfunction "SD_DAT2_69") (pintype "unspecified"))
    )
    (net (code "237") (name "unconnected-(MODULE1A-SD_DAT3-Pad61)") (class "Default")
      (node (ref "MODULE1") (pin "61") (pinfunction "SD_DAT3_61") (pintype "unspecified"))
    )
    (net (code "238") (name "unconnected-(MODULE1A-SD_DAT4-Pad68)") (class "Default")
      (node (ref "MODULE1") (pin "68") (pinfunction "SD_DAT4_68") (pintype "unspecified"))
    )
    (net (code "239") (name "unconnected-(MODULE1A-SD_DAT5-Pad64)") (class "Default")
      (node (ref "MODULE1") (pin "64") (pinfunction "SD_DAT5_64") (pintype "unspecified"))
    )
    (net (code "240") (name "unconnected-(MODULE1A-SD_DAT6-Pad72)") (class "Default")
      (node (ref "MODULE1") (pin "72") (pinfunction "SD_DAT6_72") (pintype "unspecified"))
    )
    (net (code "241") (name "unconnected-(MODULE1A-SD_DAT7-Pad70)") (class "Default")
      (node (ref "MODULE1") (pin "70") (pinfunction "SD_DAT7_70") (pintype "unspecified"))
    )
    (net (code "242") (name "unconnected-(MODULE1A-SD_PWR_ON-Pad75)") (class "Default")
      (node (ref "MODULE1") (pin "75") (pinfunction "SD_PWR_ON_75") (pintype "output"))
    )
    (net (code "243") (name "unconnected-(MODULE1A-SD_VDD_Override-Pad73)") (class "Default")
      (node (ref "MODULE1") (pin "73") (pinfunction "SD_VDD_Override_73") (pintype "input+no_connect"))
    )
    (net (code "244") (name "unconnected-(MODULE1A-VBAT-Pad76)") (class "Default")
      (node (ref "MODULE1") (pin "76") (pinfunction "VBAT_76") (pintype "unspecified+no_connect"))
    )
    (net (code "245") (name "unconnected-(MODULE1A-WiFi_nDisable-Pad89)") (class "Default")
      (node (ref "MODULE1") (pin "89") (pinfunction "WiFi_nDisable_89") (pintype "input+no_connect"))
    )
    (net (code "246") (name "unconnected-(MODULE1A-nRPIBOOT-Pad93)") (class "Default")
      (node (ref "MODULE1") (pin "93") (pinfunction "nRPIBOOT_93") (pintype "input"))
    )
    (net (code "247") (name "unconnected-(MODULE1B-GND-Pad107)") (class "Default")
      (node (ref "MODULE1") (pin "107") (pinfunction "GND_107") (pintype "unspecified"))
    )
    (net (code "248") (name "unconnected-(MODULE1B-GND-Pad108)") (class "Default")
      (node (ref "MODULE1") (pin "108") (pinfunction "GND_108") (pintype "unspecified"))
    )
    (net (code "249") (name "unconnected-(MODULE1B-GND-Pad113)") (class "Default")
      (node (ref "MODULE1") (pin "113") (pinfunction "GND_113") (pintype "unspecified"))
    )
    (net (code "250") (name "unconnected-(MODULE1B-GND-Pad114)") (class "Default")
      (node (ref "MODULE1") (pin "114") (pinfunction "GND_114") (pintype "unspecified"))
    )
    (net (code "251") (name "unconnected-(MODULE1B-GND-Pad119)") (class "Default")
      (node (ref "MODULE1") (pin "119") (pinfunction "GND_119") (pintype "unspecified"))
    )
    (net (code "252") (name "unconnected-(MODULE1B-GND-Pad120)") (class "Default")
      (node (ref "MODULE1") (pin "120") (pinfunction "GND_120") (pintype "unspecified"))
    )
    (net (code "253") (name "unconnected-(MODULE1B-GND-Pad125)") (class "Default")
      (node (ref "MODULE1") (pin "125") (pinfunction "GND_125") (pintype "unspecified"))
    )
    (net (code "254") (name "unconnected-(MODULE1B-GND-Pad126)") (class "Default")
      (node (ref "MODULE1") (pin "126") (pinfunction "GND_126") (pintype "unspecified"))
    )
    (net (code "255") (name "unconnected-(MODULE1B-GND-Pad131)") (class "Default")
      (node (ref "MODULE1") (pin "131") (pinfunction "GND_131") (pintype "unspecified"))
    )
    (net (code "256") (name "unconnected-(MODULE1B-GND-Pad132)") (class "Default")
      (node (ref "MODULE1") (pin "132") (pinfunction "GND_132") (pintype "unspecified"))
    )
    (net (code "257") (name "unconnected-(MODULE1B-GND-Pad137)") (class "Default")
      (node (ref "MODULE1") (pin "137") (pinfunction "GND_137") (pintype "unspecified"))
    )
    (net (code "258") (name "unconnected-(MODULE1B-GND-Pad138)") (class "Default")
      (node (ref "MODULE1") (pin "138") (pinfunction "GND_138") (pintype "unspecified"))
    )
    (net (code "259") (name "unconnected-(MODULE1B-GND-Pad144)") (class "Default")
      (node (ref "MODULE1") (pin "144") (pinfunction "GND_144") (pintype "unspecified"))
    )
    (net (code "260") (name "unconnected-(MODULE1B-GND-Pad150)") (class "Default")
      (node (ref "MODULE1") (pin "150") (pinfunction "GND_150") (pintype "unspecified"))
    )
    (net (code "261") (name "unconnected-(MODULE1B-GND-Pad155)") (class "Default")
      (node (ref "MODULE1") (pin "155") (pinfunction "GND_155") (pintype "unspecified"))
    )
    (net (code "262") (name "unconnected-(MODULE1B-GND-Pad156)") (class "Default")
      (node (ref "MODULE1") (pin "156") (pinfunction "GND_156") (pintype "unspecified"))
    )
    (net (code "263") (name "unconnected-(MODULE1B-GND-Pad161)") (class "Default")
      (node (ref "MODULE1") (pin "161") (pinfunction "GND_161") (pintype "unspecified"))
    )
    (net (code "264") (name "unconnected-(MODULE1B-GND-Pad162)") (class "Default")
      (node (ref "MODULE1") (pin "162") (pinfunction "GND_162") (pintype "unspecified"))
    )
    (net (code "265") (name "unconnected-(MODULE1B-GND-Pad167)") (class "Default")
      (node (ref "MODULE1") (pin "167") (pinfunction "GND_167") (pintype "unspecified"))
    )
    (net (code "266") (name "unconnected-(MODULE1B-GND-Pad168)") (class "Default")
      (node (ref "MODULE1") (pin "168") (pinfunction "GND_168") (pintype "unspecified"))
    )
    (net (code "267") (name "unconnected-(MODULE1B-GND-Pad173)") (class "Default")
      (node (ref "MODULE1") (pin "173") (pinfunction "GND_173") (pintype "unspecified"))
    )
    (net (code "268") (name "unconnected-(MODULE1B-GND-Pad174)") (class "Default")
      (node (ref "MODULE1") (pin "174") (pinfunction "GND_174") (pintype "unspecified"))
    )
    (net (code "269") (name "unconnected-(MODULE1B-GND-Pad179)") (class "Default")
      (node (ref "MODULE1") (pin "179") (pinfunction "GND_179") (pintype "unspecified"))
    )
    (net (code "270") (name "unconnected-(MODULE1B-GND-Pad180)") (class "Default")
      (node (ref "MODULE1") (pin "180") (pinfunction "GND_180") (pintype "unspecified"))
    )
    (net (code "271") (name "unconnected-(MODULE1B-GND-Pad185)") (class "Default")
      (node (ref "MODULE1") (pin "185") (pinfunction "GND_185") (pintype "unspecified"))
    )
    (net (code "272") (name "unconnected-(MODULE1B-GND-Pad186)") (class "Default")
      (node (ref "MODULE1") (pin "186") (pinfunction "GND_186") (pintype "unspecified"))
    )
    (net (code "273") (name "unconnected-(MODULE1B-GND-Pad191)") (class "Default")
      (node (ref "MODULE1") (pin "191") (pinfunction "GND_191") (pintype "unspecified"))
    )
    (net (code "274") (name "unconnected-(MODULE1B-GND-Pad192)") (class "Default")
      (node (ref "MODULE1") (pin "192") (pinfunction "GND_192") (pintype "unspecified"))
    )
    (net (code "275") (name "unconnected-(MODULE1B-GND-Pad197)") (class "Default")
      (node (ref "MODULE1") (pin "197") (pinfunction "GND_197") (pintype "unspecified"))
    )
    (net (code "276") (name "unconnected-(MODULE1B-GND-Pad198)") (class "Default")
      (node (ref "MODULE1") (pin "198") (pinfunction "GND_198") (pintype "unspecified"))
    )
    (net (code "277") (name "unconnected-(MODULE1B-HDMI0_CEC-Pad151)") (class "Default")
      (node (ref "MODULE1") (pin "151") (pinfunction "HDMI0_CEC_151") (pintype "unspecified"))
    )
    (net (code "278") (name "unconnected-(MODULE1B-HDMI0_CLK_N-Pad190)") (class "Default")
      (node (ref "MODULE1") (pin "190") (pinfunction "HDMI0_CLK_N_190") (pintype "output"))
    )
    (net (code "279") (name "unconnected-(MODULE1B-HDMI0_CLK_P-Pad188)") (class "Default")
      (node (ref "MODULE1") (pin "188") (pinfunction "HDMI0_CLK_P_188") (pintype "output"))
    )
    (net (code "280") (name "unconnected-(MODULE1B-HDMI0_HOTPLUG-Pad153)") (class "Default")
      (node (ref "MODULE1") (pin "153") (pinfunction "HDMI0_HOTPLUG_153") (pintype "input"))
    )
    (net (code "281") (name "unconnected-(MODULE1B-HDMI0_SCL-Pad200)") (class "Default")
      (node (ref "MODULE1") (pin "200") (pinfunction "HDMI0_SCL_200") (pintype "unspecified"))
    )
    (net (code "282") (name "unconnected-(MODULE1B-HDMI0_SDA-Pad199)") (class "Default")
      (node (ref "MODULE1") (pin "199") (pinfunction "HDMI0_SDA_199") (pintype "bidirectional"))
    )
    (net (code "283") (name "unconnected-(MODULE1B-HDMI0_TX0_N-Pad184)") (class "Default")
      (node (ref "MODULE1") (pin "184") (pinfunction "HDMI0_TX0_N_184") (pintype "output"))
    )
    (net (code "284") (name "unconnected-(MODULE1B-HDMI0_TX0_P-Pad182)") (class "Default")
      (node (ref "MODULE1") (pin "182") (pinfunction "HDMI0_TX0_P_182") (pintype "output"))
    )
    (net (code "285") (name "unconnected-(MODULE1B-HDMI0_TX1_N-Pad178)") (class "Default")
      (node (ref "MODULE1") (pin "178") (pinfunction "HDMI0_TX1_N_178") (pintype "output"))
    )
    (net (code "286") (name "unconnected-(MODULE1B-HDMI0_TX1_P-Pad176)") (class "Default")
      (node (ref "MODULE1") (pin "176") (pinfunction "HDMI0_TX1_P_176") (pintype "output"))
    )
    (net (code "287") (name "unconnected-(MODULE1B-HDMI0_TX2_N-Pad172)") (class "Default")
      (node (ref "MODULE1") (pin "172") (pinfunction "HDMI0_TX2_N_172") (pintype "output"))
    )
    (net (code "288") (name "unconnected-(MODULE1B-HDMI0_TX2_P-Pad170)") (class "Default")
      (node (ref "MODULE1") (pin "170") (pinfunction "HDMI0_TX2_P_170") (pintype "output"))
    )
    (net (code "289") (name "unconnected-(MODULE1B-HDMI1_CEC-Pad149)") (class "Default")
      (node (ref "MODULE1") (pin "149") (pinfunction "HDMI1_CEC_149") (pintype "unspecified"))
    )
    (net (code "290") (name "unconnected-(MODULE1B-HDMI1_CLK_N-Pad166)") (class "Default")
      (node (ref "MODULE1") (pin "166") (pinfunction "HDMI1_CLK_N_166") (pintype "output"))
    )
    (net (code "291") (name "unconnected-(MODULE1B-HDMI1_CLK_P-Pad164)") (class "Default")
      (node (ref "MODULE1") (pin "164") (pinfunction "HDMI1_CLK_P_164") (pintype "output"))
    )
    (net (code "292") (name "unconnected-(MODULE1B-HDMI1_HOTPLUG-Pad143)") (class "Default")
      (node (ref "MODULE1") (pin "143") (pinfunction "HDMI1_HOTPLUG_143") (pintype "input"))
    )
    (net (code "293") (name "unconnected-(MODULE1B-HDMI1_SCL-Pad147)") (class "Default")
      (node (ref "MODULE1") (pin "147") (pinfunction "HDMI1_SCL_147") (pintype "unspecified"))
    )
    (net (code "294") (name "unconnected-(MODULE1B-HDMI1_SDA-Pad145)") (class "Default")
      (node (ref "MODULE1") (pin "145") (pinfunction "HDMI1_SDA_145") (pintype "bidirectional"))
    )
    (net (code "295") (name "unconnected-(MODULE1B-HDMI1_TX0_N-Pad160)") (class "Default")
      (node (ref "MODULE1") (pin "160") (pinfunction "HDMI1_TX0_N_160") (pintype "output"))
    )
    (net (code "296") (name "unconnected-(MODULE1B-HDMI1_TX0_P-Pad158)") (class "Default")
      (node (ref "MODULE1") (pin "158") (pinfunction "HDMI1_TX0_P_158") (pintype "output"))
    )
    (net (code "297") (name "unconnected-(MODULE1B-HDMI1_TX1_N-Pad154)") (class "Default")
      (node (ref "MODULE1") (pin "154") (pinfunction "HDMI1_TX1_N_154") (pintype "output"))
    )
    (net (code "298") (name "unconnected-(MODULE1B-HDMI1_TX1_P-Pad152)") (class "Default")
      (node (ref "MODULE1") (pin "152") (pinfunction "HDMI1_TX1_P_152") (pintype "output"))
    )
    (net (code "299") (name "unconnected-(MODULE1B-HDMI1_TX2_N-Pad148)") (class "Default")
      (node (ref "MODULE1") (pin "148") (pinfunction "HDMI1_TX2_N_148") (pintype "output"))
    )
    (net (code "300") (name "unconnected-(MODULE1B-HDMI1_TX2_P-Pad146)") (class "Default")
      (node (ref "MODULE1") (pin "146") (pinfunction "HDMI1_TX2_P_146") (pintype "output"))
    )
    (net (code "301") (name "unconnected-(MODULE1B-MIPI0_C_N-Pad127)") (class "Default")
      (node (ref "MODULE1") (pin "127") (pinfunction "MIPI0_C_N_127") (pintype "input"))
    )
    (net (code "302") (name "unconnected-(MODULE1B-MIPI0_C_P-Pad129)") (class "Default")
      (node (ref "MODULE1") (pin "129") (pinfunction "MIPI0_C_P_129") (pintype "input"))
    )
    (net (code "303") (name "unconnected-(MODULE1B-MIPI0_D0_N-Pad115)") (class "Default")
      (node (ref "MODULE1") (pin "115") (pinfunction "MIPI0_D0_N_115") (pintype "input"))
    )
    (net (code "304") (name "unconnected-(MODULE1B-MIPI0_D0_P-Pad117)") (class "Default")
      (node (ref "MODULE1") (pin "117") (pinfunction "MIPI0_D0_P_117") (pintype "input"))
    )
    (net (code "305") (name "unconnected-(MODULE1B-MIPI0_D1_N-Pad121)") (class "Default")
      (node (ref "MODULE1") (pin "121") (pinfunction "MIPI0_D1_N_121") (pintype "input"))
    )
    (net (code "306") (name "unconnected-(MODULE1B-MIPI0_D1_P-Pad123)") (class "Default")
      (node (ref "MODULE1") (pin "123") (pinfunction "MIPI0_D1_P_123") (pintype "input"))
    )
    (net (code "307") (name "unconnected-(MODULE1B-MIPI0_D2_N-Pad133)") (class "Default")
      (node (ref "MODULE1") (pin "133") (pinfunction "MIPI0_D2_N_133") (pintype "input"))
    )
    (net (code "308") (name "unconnected-(MODULE1B-MIPI0_D2_P-Pad135)") (class "Default")
      (node (ref "MODULE1") (pin "135") (pinfunction "MIPI0_D2_P_135") (pintype "input"))
    )
    (net (code "309") (name "unconnected-(MODULE1B-MIPI0_D3_N-Pad139)") (class "Default")
      (node (ref "MODULE1") (pin "139") (pinfunction "MIPI0_D3_N_139") (pintype "input"))
    )
    (net (code "310") (name "unconnected-(MODULE1B-MIPI0_D3_P-Pad141)") (class "Default")
      (node (ref "MODULE1") (pin "141") (pinfunction "MIPI0_D3_P_141") (pintype "input"))
    )
    (net (code "311") (name "unconnected-(MODULE1B-MIPI1_C_N-Pad187)") (class "Default")
      (node (ref "MODULE1") (pin "187") (pinfunction "MIPI1_C_N_187") (pintype "output"))
    )
    (net (code "312") (name "unconnected-(MODULE1B-MIPI1_C_P-Pad189)") (class "Default")
      (node (ref "MODULE1") (pin "189") (pinfunction "MIPI1_C_P_189") (pintype "output"))
    )
    (net (code "313") (name "unconnected-(MODULE1B-MIPI1_D0_N-Pad175)") (class "Default")
      (node (ref "MODULE1") (pin "175") (pinfunction "MIPI1_D0_N_175") (pintype "output"))
    )
    (net (code "314") (name "unconnected-(MODULE1B-MIPI1_D0_P-Pad177)") (class "Default")
      (node (ref "MODULE1") (pin "177") (pinfunction "MIPI1_D0_P_177") (pintype "output"))
    )
    (net (code "315") (name "unconnected-(MODULE1B-MIPI1_D1_N-Pad181)") (class "Default")
      (node (ref "MODULE1") (pin "181") (pinfunction "MIPI1_D1_N_181") (pintype "output"))
    )
    (net (code "316") (name "unconnected-(MODULE1B-MIPI1_D1_P-Pad183)") (class "Default")
      (node (ref "MODULE1") (pin "183") (pinfunction "MIPI1_D1_P_183") (pintype "output"))
    )
    (net (code "317") (name "unconnected-(MODULE1B-MIPI1_D2_N-Pad193)") (class "Default")
      (node (ref "MODULE1") (pin "193") (pinfunction "MIPI1_D2_N_193") (pintype "output"))
    )
    (net (code "318") (name "unconnected-(MODULE1B-MIPI1_D2_P-Pad195)") (class "Default")
      (node (ref "MODULE1") (pin "195") (pinfunction "MIPI1_D2_P_195") (pintype "output"))
    )
    (net (code "319") (name "unconnected-(MODULE1B-MIPI1_D3_N-Pad194)") (class "Default")
      (node (ref "MODULE1") (pin "194") (pinfunction "MIPI1_D3_N_194") (pintype "output"))
    )
    (net (code "320") (name "unconnected-(MODULE1B-MIPI1_D3_P-Pad196)") (class "Default")
      (node (ref "MODULE1") (pin "196") (pinfunction "MIPI1_D3_P_196") (pintype "output"))
    )
    (net (code "321") (name "unconnected-(MODULE1B-PCIE_PWR_EN-Pad106)") (class "Default")
      (node (ref "MODULE1") (pin "106") (pinfunction "PCIE_PWR_EN_106") (pintype "output"))
    )
    (net (code "322") (name "unconnected-(MODULE1B-PCIE_nWAKE-Pad104)") (class "Default")
      (node (ref "MODULE1") (pin "104") (pinfunction "PCIE_nWAKE_104") (pintype "input"))
    )
    (net (code "323") (name "unconnected-(MODULE1B-PCIe_CLK_N-Pad112)") (class "Default")
      (node (ref "MODULE1") (pin "112") (pinfunction "PCIe_CLK_N_112") (pintype "output"))
    )
    (net (code "324") (name "unconnected-(MODULE1B-PCIe_CLK_P-Pad110)") (class "Default")
      (node (ref "MODULE1") (pin "110") (pinfunction "PCIe_CLK_P_110") (pintype "output"))
    )
    (net (code "325") (name "unconnected-(MODULE1B-PCIe_RX_N-Pad118)") (class "Default")
      (node (ref "MODULE1") (pin "118") (pinfunction "PCIe_RX_N_118") (pintype "input"))
    )
    (net (code "326") (name "unconnected-(MODULE1B-PCIe_RX_P-Pad116)") (class "Default")
      (node (ref "MODULE1") (pin "116") (pinfunction "PCIe_RX_P_116") (pintype "input"))
    )
    (net (code "327") (name "unconnected-(MODULE1B-PCIe_TX_N-Pad124)") (class "Default")
      (node (ref "MODULE1") (pin "124") (pinfunction "PCIe_TX_N_124") (pintype "output"))
    )
    (net (code "328") (name "unconnected-(MODULE1B-PCIe_TX_P-Pad122)") (class "Default")
      (node (ref "MODULE1") (pin "122") (pinfunction "PCIe_TX_P_122") (pintype "output"))
    )
    (net (code "329") (name "unconnected-(MODULE1B-PCIe_nCLKREQ-Pad102)") (class "Default")
      (node (ref "MODULE1") (pin "102") (pinfunction "PCIe_nCLKREQ_102") (pintype "input"))
    )
    (net (code "330") (name "unconnected-(MODULE1B-PCIe_nRST-Pad109)") (class "Default")
      (node (ref "MODULE1") (pin "109") (pinfunction "PCIe_nRST_109") (pintype "output"))
    )
    (net (code "331") (name "unconnected-(MODULE1B-USB2_N-Pad103)") (class "Default")
      (node (ref "MODULE1") (pin "103") (pinfunction "USB2_N_103") (pintype "unspecified"))
    )
    (net (code "332") (name "unconnected-(MODULE1B-USB2_P-Pad105)") (class "Default")
      (node (ref "MODULE1") (pin "105") (pinfunction "USB2_P_105") (pintype "unspecified"))
    )
    (net (code "333") (name "unconnected-(MODULE1B-USB3-0-D_N-Pad136)") (class "Default")
      (node (ref "MODULE1") (pin "136") (pinfunction "USB3-0-D_N_136") (pintype "unspecified"))
    )
    (net (code "334") (name "unconnected-(MODULE1B-USB3-0-D_P-Pad134)") (class "Default")
      (node (ref "MODULE1") (pin "134") (pinfunction "USB3-0-D_P_134") (pintype "unspecified"))
    )
    (net (code "335") (name "unconnected-(MODULE1B-USB3-0-RX_N-Pad128)") (class "Default")
      (node (ref "MODULE1") (pin "128") (pinfunction "USB3-0-RX_N_128") (pintype "input"))
    )
    (net (code "336") (name "unconnected-(MODULE1B-USB3-0-RX_P-Pad130)") (class "Default")
      (node (ref "MODULE1") (pin "130") (pinfunction "USB3-0-RX_P_130") (pintype "input"))
    )
    (net (code "337") (name "unconnected-(MODULE1B-USB3-0-TX_N-Pad140)") (class "Default")
      (node (ref "MODULE1") (pin "140") (pinfunction "USB3-0-TX_N_140") (pintype "output"))
    )
    (net (code "338") (name "unconnected-(MODULE1B-USB3-0-TX_P-Pad142)") (class "Default")
      (node (ref "MODULE1") (pin "142") (pinfunction "USB3-0-TX_P_142") (pintype "output"))
    )
    (net (code "339") (name "unconnected-(MODULE1B-USB3-1-D_N-Pad165)") (class "Default")
      (node (ref "MODULE1") (pin "165") (pinfunction "USB3-1-D_N_165") (pintype "unspecified"))
    )
    (net (code "340") (name "unconnected-(MODULE1B-USB3-1-D_P-Pad163)") (class "Default")
      (node (ref "MODULE1") (pin "163") (pinfunction "USB3-1-D_P_163") (pintype "unspecified"))
    )
    (net (code "341") (name "unconnected-(MODULE1B-USB3-1-RX_N-Pad157)") (class "Default")
      (node (ref "MODULE1") (pin "157") (pinfunction "USB3-1-RX_N_157") (pintype "input"))
    )
    (net (code "342") (name "unconnected-(MODULE1B-USB3-1-RX_P-Pad159)") (class "Default")
      (node (ref "MODULE1") (pin "159") (pinfunction "USB3-1-RX_P_159") (pintype "input"))
    )
    (net (code "343") (name "unconnected-(MODULE1B-USB3-1-TX_N-Pad169)") (class "Default")
      (node (ref "MODULE1") (pin "169") (pinfunction "USB3-1-TX_N_169") (pintype "output"))
    )
    (net (code "344") (name "unconnected-(MODULE1B-USB3-1-TX_P-Pad171)") (class "Default")
      (node (ref "MODULE1") (pin "171") (pinfunction "USB3-1-TX_P_171") (pintype "output"))
    )
    (net (code "345") (name "unconnected-(MODULE1B-USB_OTG_ID-Pad101)") (class "Default")
      (node (ref "MODULE1") (pin "101") (pinfunction "USB_OTG_ID_101") (pintype "input"))
    )
    (net (code "346") (name "unconnected-(MODULE1B-VBUS_EN-Pad111)") (class "Default")
      (node (ref "MODULE1") (pin "111") (pinfunction "VBUS_EN_111") (pintype "output"))
    )
    (net (code "347") (name "unconnected-(SW2-Pad2)") (class "Default")
      (node (ref "SW2") (pin "2") (pinfunction "2_2") (pintype "input+no_connect"))
    )
    (net (code "348") (name "unconnected-(SW2-Pad3)") (class "Default")
      (node (ref "SW2") (pin "3") (pinfunction "3_3") (pintype "input+no_connect"))
    )
    (net (code "349") (name "unconnected-(U16-NC-Pad1)") (class "Default")
      (node (ref "U16") (pin "1") (pinfunction "NC_1") (pintype "unspecified+no_connect"))
    )
  )
)
